# TAG_connect.net
KiCad netlist of a schematic drawn in EAGLE
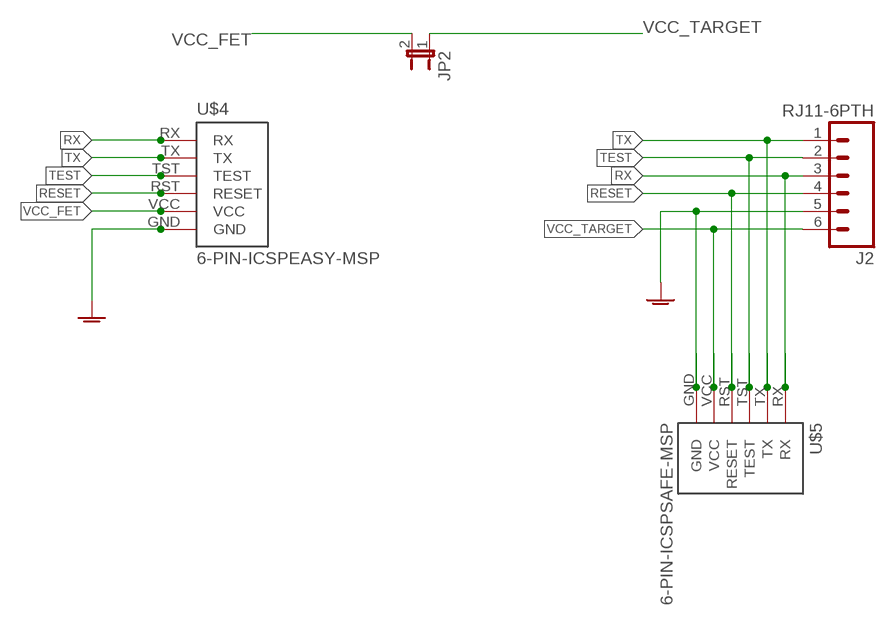
[diagram p0: schematic, sheet 1]

(export (version "E")
  (design (tool "Eeschema 10.0.6"))
  (components
    (comp (ref "J2")
      (value "RJ11-6PTH")
      (footprint "eagle-import:RJ11-6")
      (libsource (lib "eagle-import") (part "RJ11-6PTH"))
    )
    (comp (ref "JP2")
      (value "JUMPER-2PTH_LOCK")
      (footprint "eagle-import:1X02_LOCK")
      (libsource (lib "eagle-import") (part "JUMPER-2PTH_LOCK"))
    )
    (comp (ref "U$4")
      (value "6-PIN-ICSPEASY-MSP")
      (footprint "eagle-import:EASYMSP-6PIN")
      (libsource (lib "eagle-import") (part "6-PIN-ICSPEASY-MSP"))
    )
    (comp (ref "U$5")
      (value "6-PIN-ICSPSAFE-MSP")
      (footprint "eagle-import:SAFEMSP-6PIN")
      (libsource (lib "eagle-import") (part "6-PIN-ICSPSAFE-MSP"))
    )
  )
  (nets
    (net (code "1") (name "GNDA") (class "Default")
      (node (ref "J2") (pin "5") (pinfunction "5_5") (pintype "passive"))
      (node (ref "U$4") (pin "GND") (pinfunction "GND_GND") (pintype "bidirectional"))
      (node (ref "U$5") (pin "GND") (pinfunction "GND_GND") (pintype "bidirectional"))
    )
    (net (code "2") (name "RESET") (class "Default")
      (node (ref "J2") (pin "4") (pinfunction "4_4") (pintype "passive"))
      (node (ref "U$4") (pin "RST") (pinfunction "RESET_RST") (pintype "bidirectional"))
      (node (ref "U$5") (pin "RST") (pinfunction "RESET_RST") (pintype "bidirectional"))
    )
    (net (code "3") (name "RX") (class "Default")
      (node (ref "J2") (pin "3") (pinfunction "3_3") (pintype "passive"))
      (node (ref "U$4") (pin "RX") (pinfunction "RX_RX") (pintype "bidirectional"))
      (node (ref "U$5") (pin "RX") (pinfunction "RX_RX") (pintype "bidirectional"))
    )
    (net (code "4") (name "TEST") (class "Default")
      (node (ref "J2") (pin "2") (pinfunction "2_2") (pintype "passive"))
      (node (ref "U$4") (pin "TST") (pinfunction "TEST_TST") (pintype "bidirectional"))
      (node (ref "U$5") (pin "TST") (pinfunction "TEST_TST") (pintype "bidirectional"))
    )
    (net (code "5") (name "TX") (class "Default")
      (node (ref "J2") (pin "1") (pinfunction "1_1") (pintype "passive"))
      (node (ref "U$4") (pin "TX") (pinfunction "TX_TX") (pintype "bidirectional"))
      (node (ref "U$5") (pin "TX") (pinfunction "TX_TX") (pintype "bidirectional"))
    )
    (net (code "6") (name "VCC_FET") (class "Default")
      (node (ref "JP2") (pin "2") (pinfunction "2_2") (pintype "passive"))
      (node (ref "U$4") (pin "VCC") (pinfunction "VCC_VCC") (pintype "bidirectional"))
    )
    (net (code "7") (name "VCC_TARGET") (class "Default")
      (node (ref "J2") (pin "6") (pinfunction "6_6") (pintype "passive"))
      (node (ref "JP2") (pin "1") (pinfunction "1_1") (pintype "passive"))
      (node (ref "U$5") (pin "VCC") (pinfunction "VCC_VCC") (pintype "bidirectional"))
    )
  )
)
